# EEZ_AUX_PS_r4B39.net
KiCad netlist of a schematic drawn in EAGLE
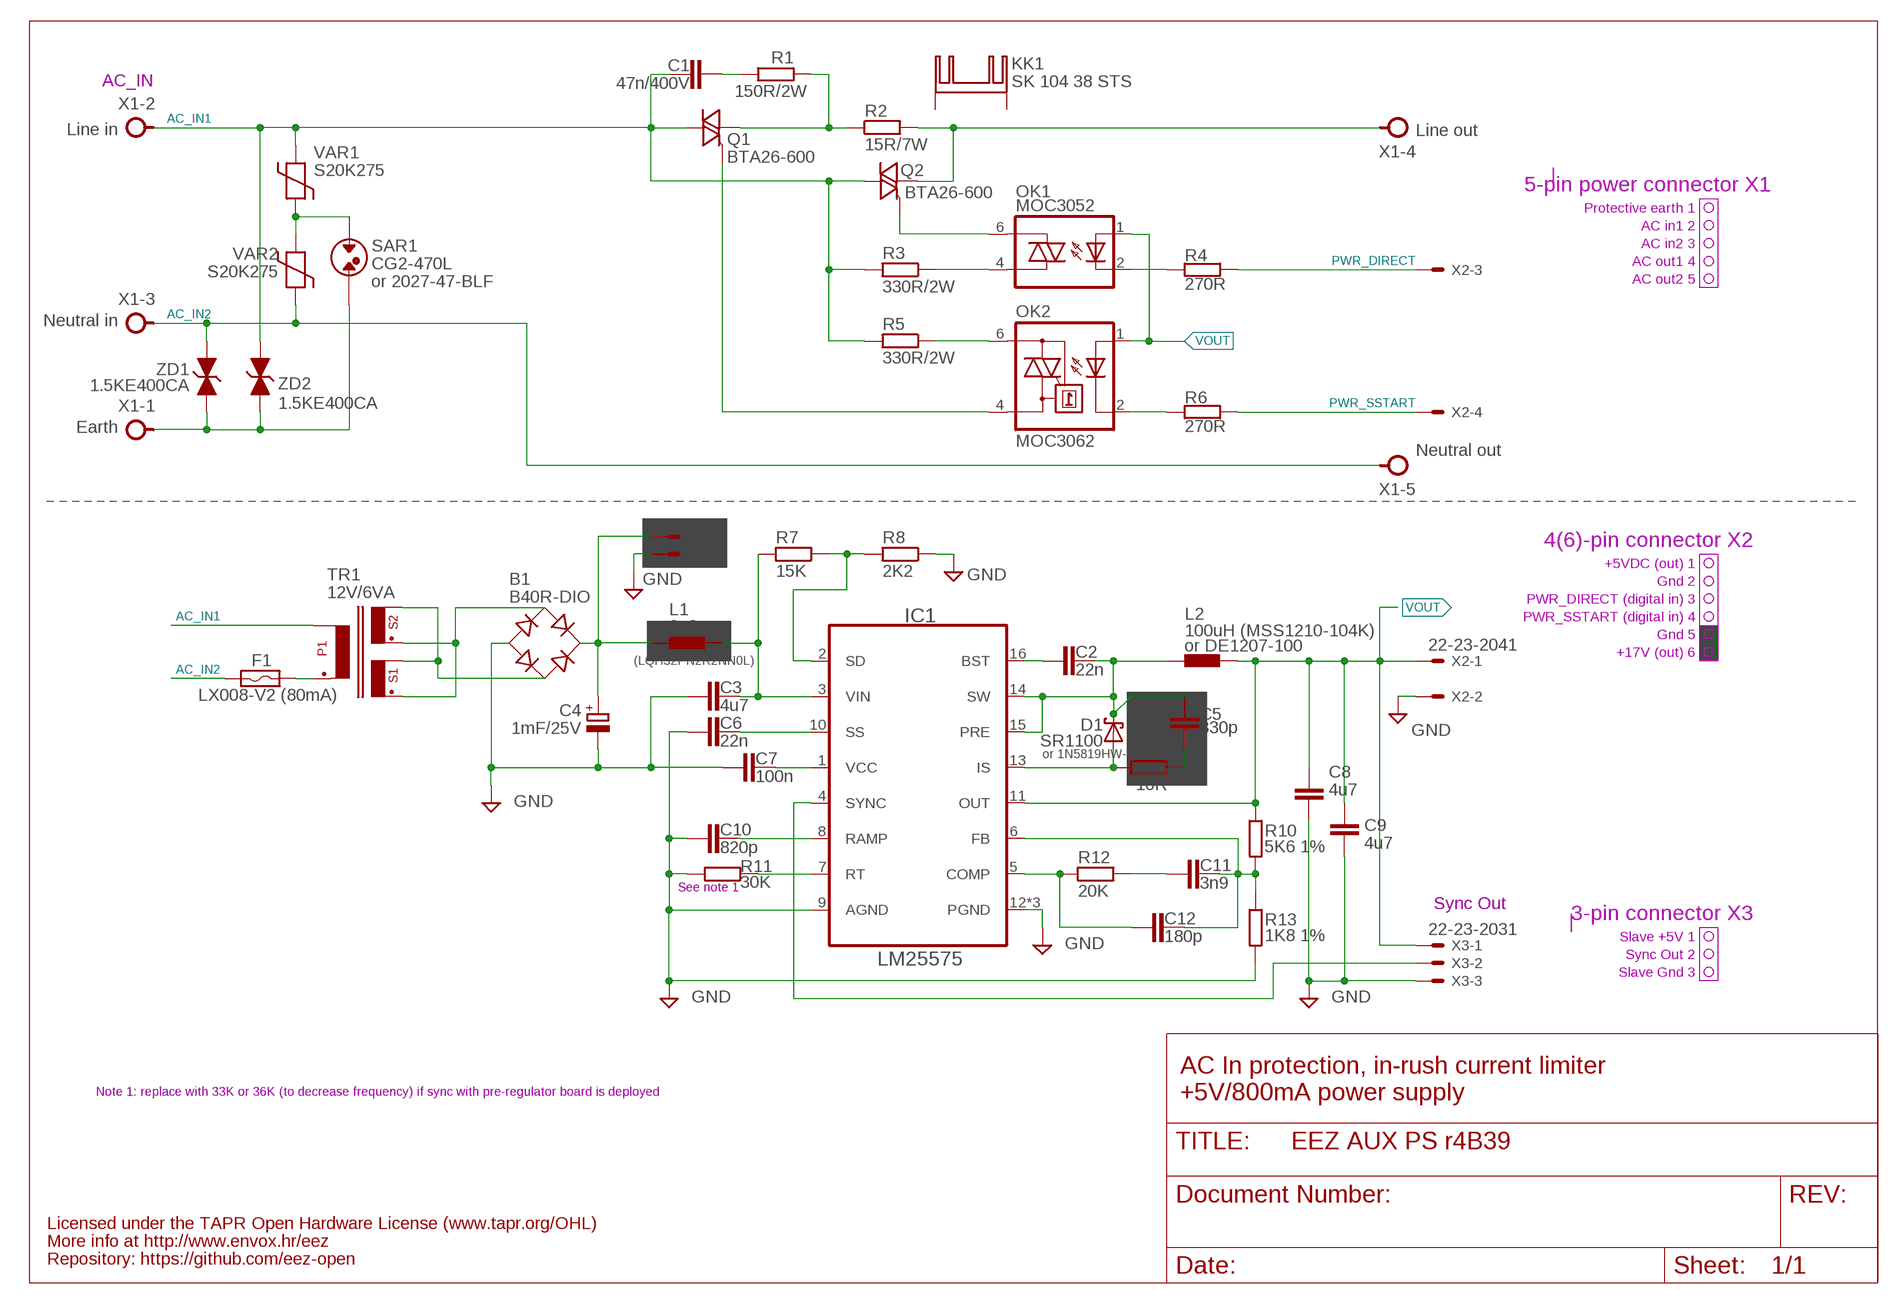
[diagram p0: schematic, sheet 1]

(export (version "E")
  (design (tool "Eeschema 10.0.6"))
  (components
    (comp (ref "B1")
      (value "B40R-DIO")
      (footprint "eagle-import:RB1A")
      (libsource (lib "eagle-import") (part "RECTIFIER-RB1A"))
    )
    (comp (ref "C1")
      (value "47n/400V")
      (footprint "eagle-import:C075-052X106")
      (libsource (lib "eagle-import") (part "C-EU075-052X106"))
    )
    (comp (ref "C2")
      (value "22n")
      (footprint "eagle-import:C0805")
      (libsource (lib "eagle-import") (part "C-EUC0805"))
    )
    (comp (ref "C3")
      (value "4u7")
      (footprint "eagle-import:C1210")
      (libsource (lib "eagle-import") (part "C-EUC1210"))
    )
    (comp (ref "C4")
      (value "1mF/25V")
      (footprint "eagle-import:ECAP5_10.5")
      (libsource (lib "eagle-import") (part "ECAP5G_10.5MM"))
    )
    (comp (ref "C5")
      (value "330p")
      (footprint "eagle-import:C0805")
      (libsource (lib "eagle-import") (part "C-EUC0805"))
    )
    (comp (ref "C6")
      (value "22n")
      (footprint "eagle-import:C0805")
      (libsource (lib "eagle-import") (part "C-EUC0805"))
    )
    (comp (ref "C7")
      (value "100n")
      (footprint "eagle-import:C0805")
      (libsource (lib "eagle-import") (part "C-EUC0805"))
    )
    (comp (ref "C8")
      (value "4u7")
      (footprint "eagle-import:C1210")
      (libsource (lib "eagle-import") (part "C-EUC1210"))
    )
    (comp (ref "C9")
      (value "4u7")
      (footprint "eagle-import:C1210")
      (libsource (lib "eagle-import") (part "C-EUC1210"))
    )
    (comp (ref "C10")
      (value "820p")
      (footprint "eagle-import:C0805")
      (libsource (lib "eagle-import") (part "C-EUC0805"))
    )
    (comp (ref "C11")
      (value "3n9")
      (footprint "eagle-import:C0805")
      (libsource (lib "eagle-import") (part "C-EUC0805"))
    )
    (comp (ref "C12")
      (value "180p")
      (footprint "eagle-import:C0805")
      (libsource (lib "eagle-import") (part "C-EUC0805"))
    )
    (comp (ref "D1")
      (value "SR1100")
      (footprint "eagle-import:DO34+SOD123")
      (libsource (lib "eagle-import") (part "SCHOTTKYDO34+SOD123"))
    )
    (comp (ref "F1")
      (value "LX008-V2 (80mA)")
      (footprint "eagle-import:POLYSWITCH-R7")
      (libsource (lib "eagle-import") (part "FUSE_RESETTABLER7"))
    )
    (comp (ref "IC1")
      (value "LM25575")
      (footprint "eagle-import:SOP65P640X110-17N_HOLE")
      (libsource (lib "eagle-import") (part "LM(2)5575"))
    )
    (comp (ref "KK1")
      (value "SK 104 38 STS")
      (footprint "eagle-import:SK409")
      (libsource (lib "eagle-import") (part "SK409"))
    )
    (comp (ref "L1")
      (value "2u2")
      (footprint "eagle-import:L1210")
      (libsource (lib "eagle-import") (part "L1210"))
    )
    (comp (ref "L2")
      (value "100uH (MSS1210-104K)")
      (footprint "eagle-import:MSS1278")
      (libsource (lib "eagle-import") (part "COILCRAFT_MSS1278"))
    )
    (comp (ref "OK1")
      (value "MOC3052")
      (footprint "eagle-import:DIL6-SMD")
      (libsource (lib "eagle-import") (part "MOC305X"))
    )
    (comp (ref "OK2")
      (value "MOC3062")
      (footprint "eagle-import:DIL6-SMD")
      (fields
        (field (name "MF") "FAIRCHILD SEMICONDUCTOR")
        (field (name "MPN") "MOC3033S-M")
        (field (name "MF_1") "FAIRCHILD SEMICONDUCTOR")
        (field (name "MPN_1") "MOC3033S-M")
        (field (name "OC_FARNELL") "unknown")
        (field (name "OC_NEWARK") "05C2878")
      )
      (libsource (lib "eagle-import") (part "MOC30S33"))
    )
    (comp (ref "Q1")
      (value "BTA26-600")
      (footprint "eagle-import:TOP3S-1")
      (libsource (lib "eagle-import") (part "BTA26-V"))
    )
    (comp (ref "Q2")
      (value "BTA26-600")
      (footprint "eagle-import:TOP3S-1")
      (libsource (lib "eagle-import") (part "BTA26-V"))
    )
    (comp (ref "R1")
      (value "150R/2W")
      (footprint "eagle-import:R2512")
      (libsource (lib "eagle-import") (part "R-EU_R2512"))
    )
    (comp (ref "R2")
      (value "15R/7W")
      (footprint "eagle-import:R_0913")
      (libsource (lib "eagle-import") (part "R_EU7W"))
    )
    (comp (ref "R3")
      (value "330R/2W")
      (footprint "eagle-import:R2512")
      (libsource (lib "eagle-import") (part "R-EU_R2512"))
    )
    (comp (ref "R4")
      (value "270R")
      (footprint "eagle-import:R0805")
      (libsource (lib "eagle-import") (part "R-EU_R0805"))
    )
    (comp (ref "R5")
      (value "330R/2W")
      (footprint "eagle-import:R2512")
      (libsource (lib "eagle-import") (part "R-EU_R2512"))
    )
    (comp (ref "R6")
      (value "270R")
      (footprint "eagle-import:R0805")
      (libsource (lib "eagle-import") (part "R-EU_R0805"))
    )
    (comp (ref "R7")
      (value "15K")
      (footprint "eagle-import:R0805")
      (libsource (lib "eagle-import") (part "R-EU_R0805"))
    )
    (comp (ref "R8")
      (value "2K2")
      (footprint "eagle-import:R0805")
      (libsource (lib "eagle-import") (part "R-EU_R0805"))
    )
    (comp (ref "R9")
      (value "10R")
      (footprint "eagle-import:R1206")
      (libsource (lib "eagle-import") (part "R-EU_R1206"))
    )
    (comp (ref "R10")
      (value "5K6 1%")
      (footprint "eagle-import:R0805")
      (libsource (lib "eagle-import") (part "R-EU_R0805"))
    )
    (comp (ref "R11")
      (value "30K")
      (footprint "eagle-import:R0805")
      (libsource (lib "eagle-import") (part "R-EU_R0805"))
    )
    (comp (ref "R12")
      (value "20K")
      (footprint "eagle-import:R0805")
      (libsource (lib "eagle-import") (part "R-EU_R0805"))
    )
    (comp (ref "R13")
      (value "1K8 1%")
      (footprint "eagle-import:R0805")
      (libsource (lib "eagle-import") (part "R-EU_R0805"))
    )
    (comp (ref "SAR1")
      (value "CG2-470L")
      (footprint "eagle-import:SAR")
      (libsource (lib "eagle-import") (part "SAR"))
    )
    (comp (ref "TR1")
      (value "12V/6VA")
      (footprint "eagle-import:PCB_TRAFO6VA_DUAL")
      (libsource (lib "eagle-import") (part "PCB_TRAFO6VACOMBO"))
    )
    (comp (ref "VAR1")
      (value "S20K275")
      (footprint "eagle-import:VARISTOR")
      (libsource (lib "eagle-import") (part "VARISTOR"))
    )
    (comp (ref "VAR2")
      (value "S20K275")
      (footprint "eagle-import:VARISTOR")
      (libsource (lib "eagle-import") (part "VARISTOR"))
    )
    (comp (ref "X1")
      (value "AC_IN")
      (footprint "eagle-import:TBLOCK5.0_5")
      (libsource (lib "eagle-import") (part "TBLOCK5.0_5A"))
    )
    (comp (ref "X2")
      (value "22-23-2041")
      (footprint "eagle-import:22-23-2061")
      (fields
        (field (name "MF") "MOLEX")
        (field (name "MPN") "22-23-2061")
        (field (name "MPN_1") "22-23-2061")
        (field (name "OC_FARNELL") "1462922")
        (field (name "OC_NEWARK") "27C1933")
      )
      (libsource (lib "eagle-import") (part "22-23-2061"))
    )
    (comp (ref "X3")
      (value "22-23-2031")
      (footprint "eagle-import:22-23-2031")
      (fields (field (name "MF") "MOLEX"))
      (libsource (lib "eagle-import") (part "22-23-2031"))
    )
    (comp (ref "ZD1")
      (value "1.5KE400CA")
      (footprint "eagle-import:DO201-BIDIR")
      (libsource (lib "eagle-import") (part "1.5KE-BIDIR"))
    )
    (comp (ref "ZD2")
      (value "1.5KE400CA")
      (footprint "eagle-import:DO201-BIDIR")
      (libsource (lib "eagle-import") (part "1.5KE-BIDIR"))
    )
  )
  (nets
    (net (code "1") (name "/AC_IN1") (class "Default")
      (node (ref "C1") (pin "2") (pinfunction "2_2") (pintype "passive"))
      (node (ref "Q1") (pin "A2") (pinfunction "A2_A2") (pintype "passive"))
      (node (ref "Q2") (pin "A2") (pinfunction "A2_A2") (pintype "passive"))
      (node (ref "R3") (pin "2") (pinfunction "2_2") (pintype "passive"))
      (node (ref "R5") (pin "2") (pinfunction "2_2") (pintype "passive"))
      (node (ref "TR1") (pin "NC1") (pinfunction "P1_NC1") (pintype "passive"))
      (node (ref "TR1") (pin "P1") (pinfunction "P1_P1") (pintype "passive"))
      (node (ref "TR1") (pin "P1.1") (pinfunction "P1_P1.1") (pintype "passive"))
      (node (ref "TR1") (pin "P1.2") (pinfunction "P1_P1.2") (pintype "passive"))
      (node (ref "VAR1") (pin "P$2") (pinfunction "P$2_P$2") (pintype "bidirectional"))
      (node (ref "X1") (pin "2") (pinfunction "1_2") (pintype "bidirectional"))
      (node (ref "ZD2") (pin "A") (pinfunction "2_A") (pintype "passive"))
    )
    (net (code "2") (name "/AC_IN2") (class "Default")
      (node (ref "F1") (pin "P$1") (pinfunction "1_P$1") (pintype "passive"))
      (node (ref "VAR2") (pin "P$1") (pinfunction "P$1_P$1") (pintype "bidirectional"))
      (node (ref "X1") (pin "3") (pinfunction "1_3") (pintype "bidirectional"))
      (node (ref "X1") (pin "5") (pinfunction "1_5") (pintype "bidirectional"))
      (node (ref "ZD1") (pin "A") (pinfunction "2_A") (pintype "passive"))
    )
    (net (code "3") (name "/PWR_DIRECT") (class "Default")
      (node (ref "R4") (pin "2") (pinfunction "2_2") (pintype "passive"))
      (node (ref "X2") (pin "3") (pinfunction "S_3") (pintype "passive"))
    )
    (net (code "4") (name "/PWR_SSTART") (class "Default")
      (node (ref "R6") (pin "2") (pinfunction "2_2") (pintype "passive"))
      (node (ref "X2") (pin "4") (pinfunction "S_4") (pintype "passive"))
    )
    (net (code "5") (name "GND") (class "Default")
      (node (ref "B1") (pin "-") (pinfunction "-_-") (pintype "passive"))
      (node (ref "C10") (pin "1") (pinfunction "1_1") (pintype "passive"))
      (node (ref "C3") (pin "2") (pinfunction "2_2") (pintype "passive"))
      (node (ref "C4") (pin "-") (pinfunction "-_-") (pintype "passive"))
      (node (ref "C6") (pin "2") (pinfunction "2_2") (pintype "passive"))
      (node (ref "C7") (pin "1") (pinfunction "1_1") (pintype "passive"))
      (node (ref "C8") (pin "2") (pinfunction "2_2") (pintype "passive"))
      (node (ref "C9") (pin "2") (pinfunction "2_2") (pintype "passive"))
      (node (ref "IC1") (pin "12") (pinfunction "PGND_12") (pintype "passive"))
      (node (ref "IC1") (pin "9") (pinfunction "AGND_9") (pintype "passive"))
      (node (ref "IC1") (pin "TP") (pinfunction "PGND_TP") (pintype "passive"))
      (node (ref "IC1") (pin "TP2") (pinfunction "PGND_TP2") (pintype "passive"))
      (node (ref "R11") (pin "2") (pinfunction "2_2") (pintype "passive"))
      (node (ref "R13") (pin "2") (pinfunction "2_2") (pintype "passive"))
      (node (ref "R8") (pin "1") (pinfunction "1_1") (pintype "passive"))
      (node (ref "X2") (pin "2") (pinfunction "S_2") (pintype "passive"))
      (node (ref "X2") (pin "5") (pinfunction "S_5") (pintype "passive"))
      (node (ref "X3") (pin "3") (pinfunction "S_3") (pintype "passive"))
    )
    (net (code "6") (name "Net-(B1-PadAC1)") (class "Default")
      (node (ref "B1") (pin "AC1") (pinfunction "AC1_AC1") (pintype "passive"))
      (node (ref "TR1") (pin "S1.1") (pinfunction "S1.1_S1.1") (pintype "passive"))
      (node (ref "TR1") (pin "S2.1") (pinfunction "S2.1_S2.1") (pintype "passive"))
      (node (ref "TR1") (pin "S2.1A") (pinfunction "S2.1_S2.1A") (pintype "passive"))
    )
    (net (code "7") (name "Net-(B1-PadAC2)") (class "Default")
      (node (ref "B1") (pin "AC2") (pinfunction "AC2_AC2") (pintype "passive"))
      (node (ref "TR1") (pin "S1.2") (pinfunction "S1.2_S1.2") (pintype "passive"))
      (node (ref "TR1") (pin "S1.2A") (pinfunction "S1.2_S1.2A") (pintype "passive"))
      (node (ref "TR1") (pin "S1.2NC") (pinfunction "S1.2_S1.2NC") (pintype "passive"))
      (node (ref "TR1") (pin "S2.2") (pinfunction "S2.2_S2.2") (pintype "passive"))
    )
    (net (code "8") (name "Net-(C1-Pad1)") (class "Default")
      (node (ref "C1") (pin "1") (pinfunction "1_1") (pintype "passive"))
      (node (ref "R1") (pin "1") (pinfunction "1_1") (pintype "passive"))
    )
    (net (code "9") (name "Net-(C5-Pad2)") (class "Default")
      (node (ref "C5") (pin "2") (pinfunction "2_2") (pintype "passive"))
      (node (ref "R9") (pin "2") (pinfunction "2_2") (pintype "passive"))
    )
    (net (code "10") (name "Net-(C11-Pad2)") (class "Default")
      (node (ref "C11") (pin "2") (pinfunction "2_2") (pintype "passive"))
      (node (ref "R12") (pin "2") (pinfunction "2_2") (pintype "passive"))
    )
    (net (code "11") (name "Net-(F1-2)") (class "Default")
      (node (ref "F1") (pin "P$2") (pinfunction "2_P$2") (pintype "passive"))
      (node (ref "TR1") (pin "P2") (pinfunction "P2_P2") (pintype "passive"))
      (node (ref "TR1") (pin "P2.1") (pinfunction "P2_P2.1") (pintype "passive"))
      (node (ref "TR1") (pin "P2.2") (pinfunction "P2_P2.2") (pintype "passive"))
    )
    (net (code "12") (name "Net-(IC1-BST)") (class "Default")
      (node (ref "C2") (pin "2") (pinfunction "2_2") (pintype "passive"))
      (node (ref "IC1") (pin "16") (pinfunction "BST_16") (pintype "input"))
    )
    (net (code "13") (name "Net-(IC1-COMP)") (class "Default")
      (node (ref "C12") (pin "2") (pinfunction "2_2") (pintype "passive"))
      (node (ref "IC1") (pin "5") (pinfunction "COMP_5") (pintype "input"))
      (node (ref "R12") (pin "1") (pinfunction "1_1") (pintype "passive"))
    )
    (net (code "14") (name "Net-(IC1-FB)") (class "Default")
      (node (ref "C11") (pin "1") (pinfunction "1_1") (pintype "passive"))
      (node (ref "C12") (pin "1") (pinfunction "1_1") (pintype "passive"))
      (node (ref "IC1") (pin "6") (pinfunction "FB_6") (pintype "input"))
      (node (ref "R10") (pin "2") (pinfunction "2_2") (pintype "passive"))
      (node (ref "R13") (pin "1") (pinfunction "1_1") (pintype "passive"))
    )
    (net (code "15") (name "Net-(IC1-IS)") (class "Default")
      (node (ref "D1") (pin "A") (pinfunction "A_A") (pintype "passive"))
      (node (ref "D1") (pin "A.1") (pinfunction "A_A.1") (pintype "passive"))
      (node (ref "IC1") (pin "13") (pinfunction "IS_13") (pintype "input"))
      (node (ref "R9") (pin "1") (pinfunction "1_1") (pintype "passive"))
    )
    (net (code "16") (name "Net-(IC1-PRE)") (class "Default")
      (node (ref "C2") (pin "1") (pinfunction "1_1") (pintype "passive"))
      (node (ref "C5") (pin "1") (pinfunction "1_1") (pintype "passive"))
      (node (ref "D1") (pin "C") (pinfunction "C_C") (pintype "passive"))
      (node (ref "D1") (pin "C.1") (pinfunction "C_C.1") (pintype "passive"))
      (node (ref "IC1") (pin "14") (pinfunction "SW_14") (pintype "output"))
      (node (ref "IC1") (pin "15") (pinfunction "PRE_15") (pintype "input"))
      (node (ref "L2") (pin "1") (pinfunction "1_1") (pintype "passive"))
    )
    (net (code "17") (name "Net-(IC1-RAMP)") (class "Default")
      (node (ref "C10") (pin "2") (pinfunction "2_2") (pintype "passive"))
      (node (ref "IC1") (pin "8") (pinfunction "RAMP_8") (pintype "input"))
    )
    (net (code "18") (name "Net-(IC1-RT)") (class "Default")
      (node (ref "IC1") (pin "7") (pinfunction "RT_7") (pintype "input"))
      (node (ref "R11") (pin "1") (pinfunction "1_1") (pintype "passive"))
    )
    (net (code "19") (name "Net-(IC1-SD)") (class "Default")
      (node (ref "IC1") (pin "2") (pinfunction "SD_2") (pintype "input"))
      (node (ref "R7") (pin "1") (pinfunction "1_1") (pintype "passive"))
      (node (ref "R8") (pin "2") (pinfunction "2_2") (pintype "passive"))
    )
    (net (code "20") (name "Net-(IC1-SS)") (class "Default")
      (node (ref "C6") (pin "1") (pinfunction "1_1") (pintype "passive"))
      (node (ref "IC1") (pin "10") (pinfunction "SS_10") (pintype "input"))
    )
    (net (code "21") (name "Net-(IC1-SYNC)") (class "Default")
      (node (ref "IC1") (pin "4") (pinfunction "SYNC_4") (pintype "input"))
      (node (ref "X3") (pin "2") (pinfunction "S_2") (pintype "passive"))
    )
    (net (code "22") (name "Net-(IC1-VCC)") (class "Default")
      (node (ref "C7") (pin "2") (pinfunction "2_2") (pintype "passive"))
      (node (ref "IC1") (pin "1") (pinfunction "VCC_1") (pintype "power_in"))
    )
    (net (code "23") (name "Net-(IC1-VIN)") (class "Default")
      (node (ref "C3") (pin "1") (pinfunction "1_1") (pintype "passive"))
      (node (ref "IC1") (pin "3") (pinfunction "VIN_3") (pintype "input"))
      (node (ref "L1") (pin "2") (pinfunction "2_2") (pintype "passive"))
      (node (ref "R7") (pin "2") (pinfunction "2_2") (pintype "passive"))
    )
    (net (code "24") (name "Net-(OK1-A1)") (class "Default")
      (node (ref "OK1") (pin "4") (pinfunction "A1_4") (pintype "passive"))
      (node (ref "R3") (pin "1") (pinfunction "1_1") (pintype "passive"))
    )
    (net (code "25") (name "Net-(OK1-A2)") (class "Default")
      (node (ref "OK1") (pin "6") (pinfunction "A2_6") (pintype "passive"))
      (node (ref "Q2") (pin "G") (pinfunction "G_G") (pintype "passive"))
    )
    (net (code "26") (name "Net-(OK1-C)") (class "Default")
      (node (ref "OK1") (pin "2") (pinfunction "C_2") (pintype "passive"))
      (node (ref "R4") (pin "1") (pinfunction "1_1") (pintype "passive"))
    )
    (net (code "27") (name "Net-(OK2-A1)") (class "Default")
      (node (ref "OK2") (pin "4") (pinfunction "A1_4") (pintype "passive"))
      (node (ref "Q1") (pin "G") (pinfunction "G_G") (pintype "passive"))
    )
    (net (code "28") (name "Net-(OK2-A2)") (class "Default")
      (node (ref "OK2") (pin "6") (pinfunction "A2_6") (pintype "passive"))
      (node (ref "R5") (pin "1") (pinfunction "1_1") (pintype "passive"))
    )
    (net (code "29") (name "Net-(OK2-C)") (class "Default")
      (node (ref "OK2") (pin "2") (pinfunction "C_2") (pintype "passive"))
      (node (ref "R6") (pin "1") (pinfunction "1_1") (pintype "passive"))
    )
    (net (code "30") (name "Net-(Q1-PadA1)") (class "Default")
      (node (ref "Q1") (pin "A1") (pinfunction "A1_A1") (pintype "passive"))
      (node (ref "R1") (pin "2") (pinfunction "2_2") (pintype "passive"))
      (node (ref "R2") (pin "1") (pinfunction "1_1") (pintype "passive"))
    )
    (net (code "31") (name "Net-(SAR1-PadP$1)") (class "Default")
      (node (ref "SAR1") (pin "P$1") (pinfunction "P$1_P$1") (pintype "bidirectional"))
      (node (ref "VAR1") (pin "P$1") (pinfunction "P$1_P$1") (pintype "bidirectional"))
      (node (ref "VAR2") (pin "P$2") (pinfunction "P$2_P$2") (pintype "bidirectional"))
    )
    (net (code "32") (name "Net-(X1D-1)") (class "Default")
      (node (ref "Q2") (pin "A1") (pinfunction "A1_A1") (pintype "passive"))
      (node (ref "R2") (pin "2") (pinfunction "2_2") (pintype "passive"))
      (node (ref "X1") (pin "4") (pinfunction "1_4") (pintype "bidirectional"))
    )
    (net (code "33") (name "Net-(X2F-S)") (class "Default")
      (node (ref "B1") (pin "+") (pinfunction "+_+") (pintype "passive"))
      (node (ref "C4") (pin "+") (pinfunction "+_+") (pintype "passive"))
      (node (ref "L1") (pin "1") (pinfunction "1_1") (pintype "passive"))
      (node (ref "X2") (pin "6") (pinfunction "S_6") (pintype "passive"))
    )
    (net (code "34") (name "Net-(ZD1-1)") (class "Default")
      (node (ref "SAR1") (pin "P$2") (pinfunction "P$2_P$2") (pintype "bidirectional"))
      (node (ref "X1") (pin "1") (pinfunction "1_1") (pintype "bidirectional"))
      (node (ref "ZD1") (pin "C") (pinfunction "1_C") (pintype "passive"))
      (node (ref "ZD2") (pin "C") (pinfunction "1_C") (pintype "passive"))
    )
    (net (code "35") (name "VOUT") (class "Default")
      (node (ref "C8") (pin "1") (pinfunction "1_1") (pintype "passive"))
      (node (ref "C9") (pin "1") (pinfunction "1_1") (pintype "passive"))
      (node (ref "IC1") (pin "11") (pinfunction "OUT_11") (pintype "output"))
      (node (ref "L2") (pin "2") (pinfunction "2_2") (pintype "passive"))
      (node (ref "OK1") (pin "1") (pinfunction "A_1") (pintype "passive"))
      (node (ref "OK2") (pin "1") (pinfunction "A_1") (pintype "passive"))
      (node (ref "R10") (pin "1") (pinfunction "1_1") (pintype "passive"))
      (node (ref "X2") (pin "1") (pinfunction "S_1") (pintype "passive"))
      (node (ref "X3") (pin "1") (pinfunction "S_1") (pintype "passive"))
    )
    (net (code "36") (name "unconnected-(KK1-K-PadK1)") (class "Default")
      (node (ref "KK1") (pin "K1") (pinfunction "K_K1") (pintype "passive"))
    )
    (net (code "37") (name "unconnected-(KK1-K-PadK2)") (class "Default")
      (node (ref "KK1") (pin "K2") (pinfunction "K_K2") (pintype "passive"))
    )
  )
)
